# LDVBug_Hauptplatine.net
KiCad netlist of a schematic drawn in EAGLE
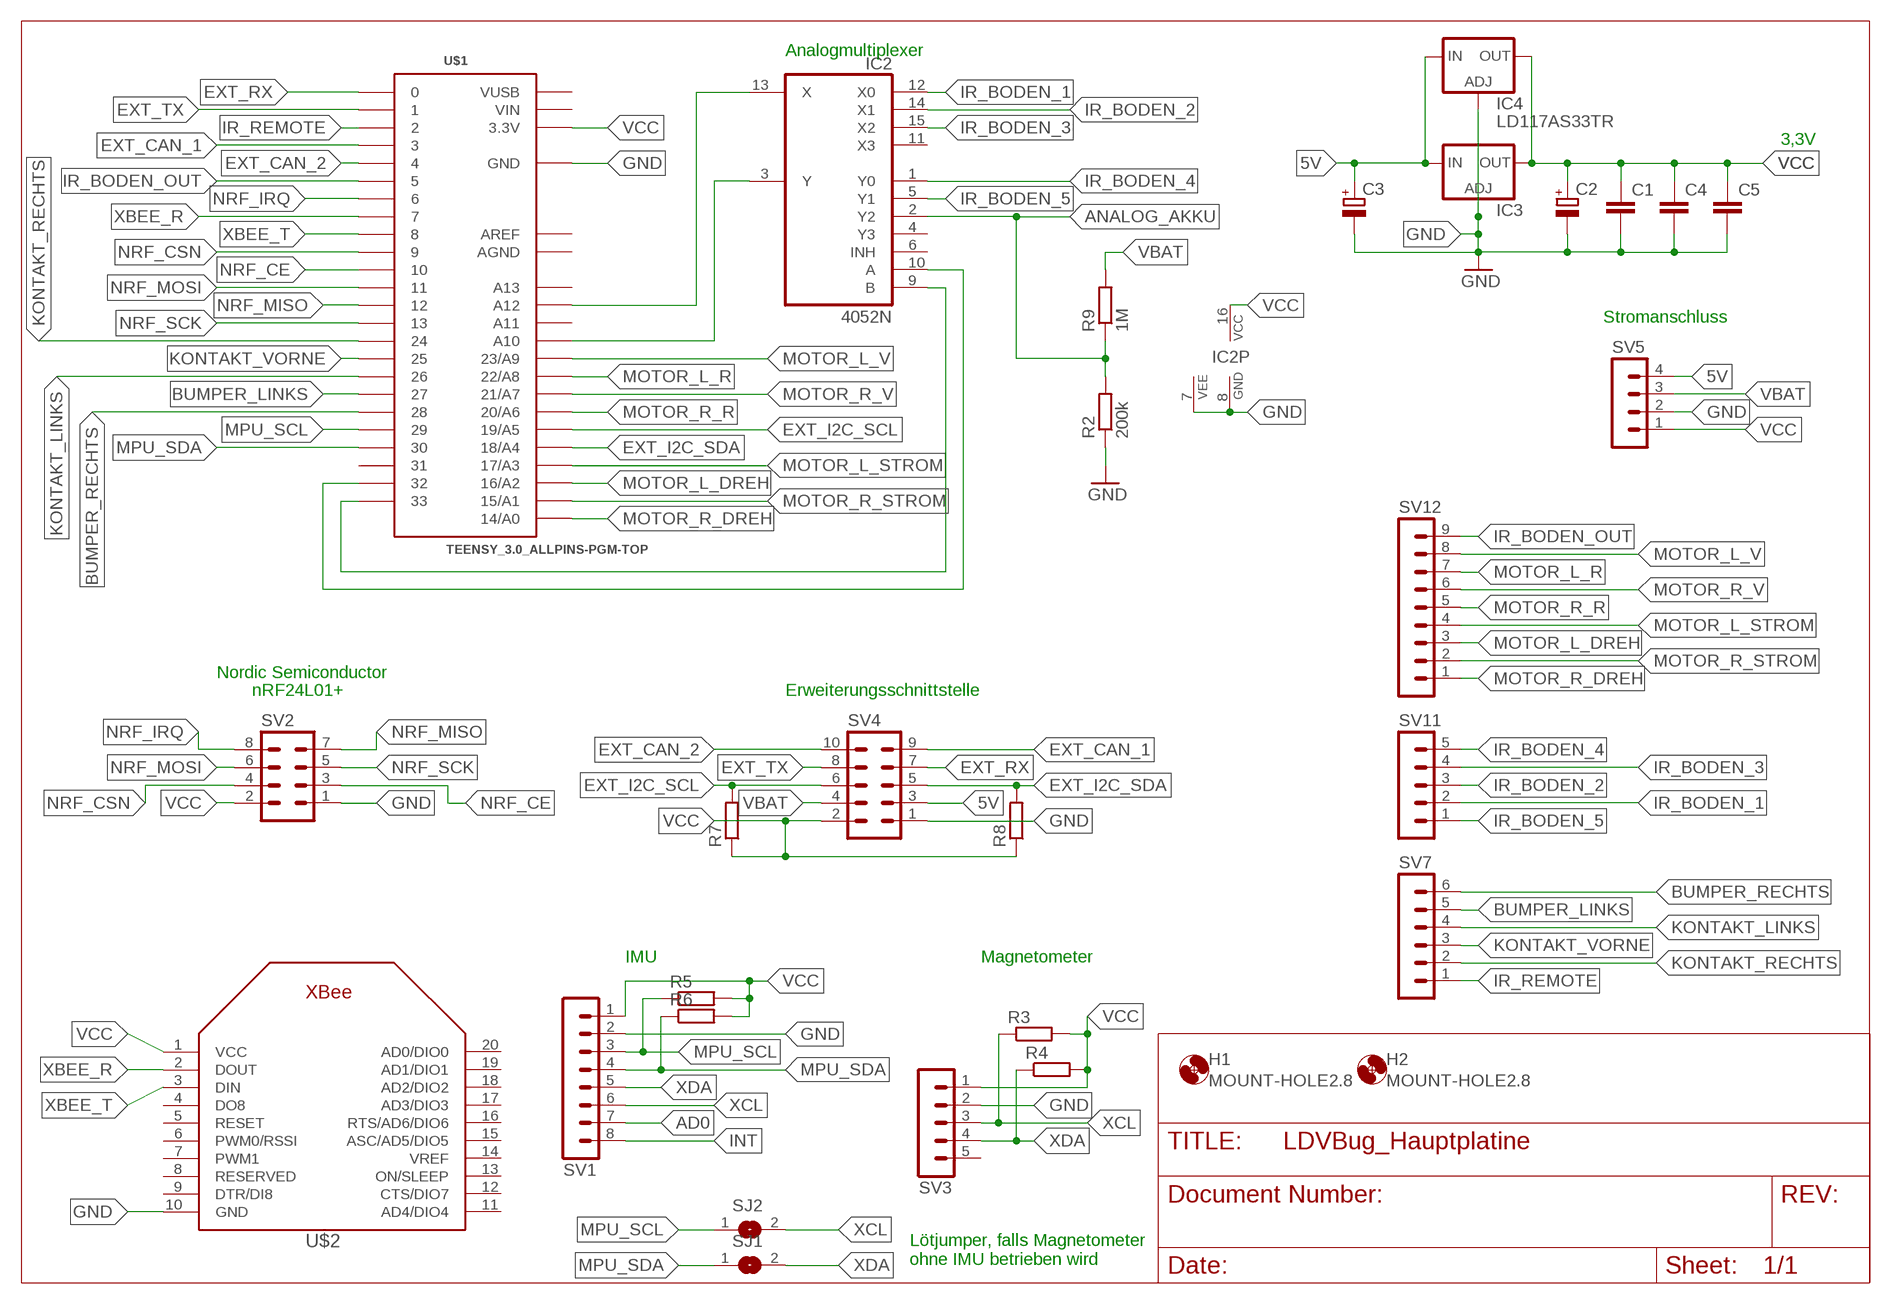
[diagram p0: schematic, sheet 1]

(export (version "E")
  (design (tool "Eeschema 10.0.6"))
  (components
    (comp (ref "C1")
      (value "C-EU025-025X050")
      (footprint "eagle-import:C025-025X050")
      (libsource (lib "eagle-import") (part "C-EU025-025X050"))
    )
    (comp (ref "C2")
      (value "CPOL-EUE2.5-7")
      (footprint "eagle-import:E2,5-7")
      (libsource (lib "eagle-import") (part "CPOL-EUE2.5-7"))
    )
    (comp (ref "C3")
      (value "CPOL-EUE2.5-7")
      (footprint "eagle-import:E2,5-7")
      (libsource (lib "eagle-import") (part "CPOL-EUE2.5-7"))
    )
    (comp (ref "C4")
      (value "C-EU025-025X050")
      (footprint "eagle-import:C025-025X050")
      (libsource (lib "eagle-import") (part "C-EU025-025X050"))
    )
    (comp (ref "C5")
      (value "C-EU025-025X050")
      (footprint "eagle-import:C025-025X050")
      (libsource (lib "eagle-import") (part "C-EU025-025X050"))
    )
    (comp (ref "H1")
      (value "MOUNT-HOLE2.8")
      (footprint "eagle-import:2,8")
      (libsource (lib "eagle-import") (part "MOUNT-HOLE2.8"))
    )
    (comp (ref "H2")
      (value "MOUNT-HOLE2.8")
      (footprint "eagle-import:2,8")
      (libsource (lib "eagle-import") (part "MOUNT-HOLE2.8"))
    )
    (comp (ref "IC2")
      (value "4052N")
      (footprint "eagle-import:DIL16")
      (libsource (lib "eagle-import") (part "4052N"))
    )
    (comp (ref "IC3")
      (value "LM317TS")
      (footprint "eagle-import:317TS")
      (libsource (lib "eagle-import") (part "LM317TS"))
    )
    (comp (ref "IC4")
      (value "LD117AS33TR")
      (footprint "eagle-import:SOT223")
      (libsource (lib "eagle-import") (part "LD117A?S33TR"))
    )
    (comp (ref "R2")
      (value "200k")
      (footprint "eagle-import:0207_10")
      (libsource (lib "eagle-import") (part "R-EU_0207/10"))
    )
    (comp (ref "R3")
      (value "R-EU_R0805")
      (footprint "eagle-import:R0805")
      (libsource (lib "eagle-import") (part "R-EU_R0805"))
    )
    (comp (ref "R4")
      (value "R-EU_R0805")
      (footprint "eagle-import:R0805")
      (libsource (lib "eagle-import") (part "R-EU_R0805"))
    )
    (comp (ref "R5")
      (value "R-EU_R0805")
      (footprint "eagle-import:R0805")
      (libsource (lib "eagle-import") (part "R-EU_R0805"))
    )
    (comp (ref "R6")
      (value "R-EU_R0805")
      (footprint "eagle-import:R0805")
      (libsource (lib "eagle-import") (part "R-EU_R0805"))
    )
    (comp (ref "R7")
      (value "R-EU_R0805")
      (footprint "eagle-import:R0805")
      (libsource (lib "eagle-import") (part "R-EU_R0805"))
    )
    (comp (ref "R8")
      (value "R-EU_R0805")
      (footprint "eagle-import:R0805")
      (libsource (lib "eagle-import") (part "R-EU_R0805"))
    )
    (comp (ref "R9")
      (value "1M")
      (footprint "eagle-import:0207_15")
      (libsource (lib "eagle-import") (part "R-EU_0207/18"))
    )
    (comp (ref "SJ1") (value "SJ") (footprint "eagle-import:SJ") (libsource (lib "eagle-import") (part "SJ")))
    (comp (ref "SJ2") (value "SJ") (footprint "eagle-import:SJ") (libsource (lib "eagle-import") (part "SJ")))
    (comp (ref "SV1")
      (value "MA08-1")
      (footprint "eagle-import:MA08-1")
      (libsource (lib "eagle-import") (part "MA08-1"))
    )
    (comp (ref "SV2")
      (value "MA04-2")
      (footprint "eagle-import:MA04-2")
      (libsource (lib "eagle-import") (part "MA04-2"))
    )
    (comp (ref "SV3")
      (value "MA05-1")
      (footprint "eagle-import:MA05-1")
      (libsource (lib "eagle-import") (part "MA05-1"))
    )
    (comp (ref "SV4")
      (value "MA05-2")
      (footprint "eagle-import:MA05-2")
      (libsource (lib "eagle-import") (part "MA05-2"))
    )
    (comp (ref "SV5")
      (value "MA04-1")
      (footprint "eagle-import:MA04-1")
      (libsource (lib "eagle-import") (part "MA04-1"))
    )
    (comp (ref "SV7")
      (value "MA06-1")
      (footprint "eagle-import:MA06-1")
      (libsource (lib "eagle-import") (part "MA06-1"))
    )
    (comp (ref "SV11")
      (value "MA05-1")
      (footprint "eagle-import:MA05-1")
      (libsource (lib "eagle-import") (part "MA05-1"))
    )
    (comp (ref "SV12")
      (value "MA09-1")
      (footprint "eagle-import:MA09-1")
      (libsource (lib "eagle-import") (part "MA09-1"))
    )
    (comp (ref "U$1")
      (value "TEENSY_3.0_ALLPINS-PGM-TOP")
      (footprint "eagle-import:TEENSY_3.0_ALLPINS-PGM")
      (libsource (lib "eagle-import") (part "TEENSY_3.0_ALLPINS-PGM-TOP"))
    )
    (comp (ref "U$2")
      (value "XBEE")
      (footprint "eagle-import:XBEE")
      (libsource (lib "eagle-import") (part "XBEE"))
    )
  )
  (nets
    (net (code "1") (name "/AGND") (class "Default")
      (node (ref "U$1") (pin "AGND") (pinfunction "AGND_AGND") (pintype "power_in"))
    )
    (net (code "2") (name "/AREF") (class "Default")
      (node (ref "U$1") (pin "AREF") (pinfunction "AREF_AREF") (pintype "power_in"))
    )
    (net (code "3") (name "/VIN") (class "Default")
      (node (ref "U$1") (pin "VIN") (pinfunction "VIN_VIN") (pintype "power_in"))
    )
    (net (code "4") (name "/VUSB") (class "Default")
      (node (ref "U$1") (pin "VUSB") (pinfunction "VUSB_VUSB") (pintype "power_in"))
    )
    (net (code "5") (name "5V") (class "Default")
      (node (ref "C3") (pin "+") (pinfunction "+_+") (pintype "passive"))
      (node (ref "IC3") (pin "3") (pinfunction "IN_3") (pintype "input"))
      (node (ref "IC4") (pin "3") (pinfunction "IN_3") (pintype "input"))
      (node (ref "SV4") (pin "3") (pinfunction "3_3") (pintype "passive"))
      (node (ref "SV5") (pin "4") (pinfunction "4_4") (pintype "passive"))
    )
    (net (code "6") (name "AD0") (class "Default")
      (node (ref "SV1") (pin "7") (pinfunction "7_7") (pintype "passive"))
    )
    (net (code "7") (name "ANALOG_AKKU") (class "Default")
      (node (ref "IC2") (pin "2") (pinfunction "Y2_2") (pintype "bidirectional"))
      (node (ref "R2") (pin "2") (pinfunction "2_2") (pintype "passive"))
      (node (ref "R9") (pin "1") (pinfunction "1_1") (pintype "passive"))
    )
    (net (code "8") (name "BUMPER_LINKS") (class "Default")
      (node (ref "SV7") (pin "5") (pinfunction "5_5") (pintype "passive"))
      (node (ref "U$1") (pin "27") (pinfunction "27_27") (pintype "bidirectional"))
    )
    (net (code "9") (name "BUMPER_RECHTS") (class "Default")
      (node (ref "SV7") (pin "6") (pinfunction "6_6") (pintype "passive"))
      (node (ref "U$1") (pin "28") (pinfunction "28_28") (pintype "bidirectional"))
    )
    (net (code "10") (name "EXT_CAN_1") (class "Default")
      (node (ref "SV4") (pin "9") (pinfunction "9_9") (pintype "passive"))
      (node (ref "U$1") (pin "3") (pinfunction "3_3") (pintype "bidirectional"))
    )
    (net (code "11") (name "EXT_CAN_2") (class "Default")
      (node (ref "SV4") (pin "10") (pinfunction "10_10") (pintype "passive"))
      (node (ref "U$1") (pin "4") (pinfunction "4_4") (pintype "bidirectional"))
    )
    (net (code "12") (name "EXT_I2C_SCL") (class "Default")
      (node (ref "R7") (pin "2") (pinfunction "2_2") (pintype "passive"))
      (node (ref "SV4") (pin "6") (pinfunction "6_6") (pintype "passive"))
      (node (ref "U$1") (pin "19/A5") (pinfunction "19/A5_19/A5") (pintype "bidirectional"))
    )
    (net (code "13") (name "EXT_I2C_SDA") (class "Default")
      (node (ref "R8") (pin "2") (pinfunction "2_2") (pintype "passive"))
      (node (ref "SV4") (pin "5") (pinfunction "5_5") (pintype "passive"))
      (node (ref "U$1") (pin "18/A4") (pinfunction "18/A4_18/A4") (pintype "bidirectional"))
    )
    (net (code "14") (name "EXT_RX") (class "Default")
      (node (ref "SV4") (pin "7") (pinfunction "7_7") (pintype "passive"))
      (node (ref "U$1") (pin "0") (pinfunction "0_0") (pintype "bidirectional"))
    )
    (net (code "15") (name "EXT_TX") (class "Default")
      (node (ref "SV4") (pin "8") (pinfunction "8_8") (pintype "passive"))
      (node (ref "U$1") (pin "1") (pinfunction "1_1") (pintype "bidirectional"))
    )
    (net (code "16") (name "GND") (class "Default")
      (node (ref "C1") (pin "2") (pinfunction "2_2") (pintype "passive"))
      (node (ref "C2") (pin "-") (pinfunction "-_-") (pintype "passive"))
      (node (ref "C3") (pin "-") (pinfunction "-_-") (pintype "passive"))
      (node (ref "C4") (pin "2") (pinfunction "2_2") (pintype "passive"))
      (node (ref "C5") (pin "2") (pinfunction "2_2") (pintype "passive"))
      (node (ref "IC2") (pin "7") (pinfunction "VEE_7") (pintype "power_in"))
      (node (ref "IC2") (pin "8") (pinfunction "GND_8") (pintype "power_in"))
      (node (ref "IC3") (pin "1") (pinfunction "ADJ_1") (pintype "input"))
      (node (ref "IC4") (pin "1") (pinfunction "ADJ_1") (pintype "input"))
      (node (ref "R2") (pin "1") (pinfunction "1_1") (pintype "passive"))
      (node (ref "SV1") (pin "2") (pinfunction "2_2") (pintype "passive"))
      (node (ref "SV2") (pin "1") (pinfunction "1_1") (pintype "passive"))
      (node (ref "SV3") (pin "2") (pinfunction "2_2") (pintype "passive"))
      (node (ref "SV4") (pin "1") (pinfunction "1_1") (pintype "passive"))
      (node (ref "SV5") (pin "2") (pinfunction "2_2") (pintype "passive"))
      (node (ref "U$1") (pin "GND") (pinfunction "GND_GND") (pintype "power_in"))
      (node (ref "U$1") (pin "GND2") (pinfunction "GND_GND2") (pintype "power_in"))
      (node (ref "U$2") (pin "10") (pinfunction "GND_10") (pintype "power_in"))
    )
    (net (code "17") (name "INT") (class "Default")
      (node (ref "SV1") (pin "8") (pinfunction "8_8") (pintype "passive"))
    )
    (net (code "18") (name "IR_BODEN_1") (class "Default")
      (node (ref "IC2") (pin "12") (pinfunction "X0_12") (pintype "bidirectional"))
      (node (ref "SV11") (pin "2") (pinfunction "2_2") (pintype "passive"))
    )
    (net (code "19") (name "IR_BODEN_2") (class "Default")
      (node (ref "IC2") (pin "14") (pinfunction "X1_14") (pintype "bidirectional"))
      (node (ref "SV11") (pin "3") (pinfunction "3_3") (pintype "passive"))
    )
    (net (code "20") (name "IR_BODEN_3") (class "Default")
      (node (ref "IC2") (pin "15") (pinfunction "X2_15") (pintype "bidirectional"))
      (node (ref "SV11") (pin "4") (pinfunction "4_4") (pintype "passive"))
    )
    (net (code "21") (name "IR_BODEN_4") (class "Default")
      (node (ref "IC2") (pin "1") (pinfunction "Y0_1") (pintype "bidirectional"))
      (node (ref "SV11") (pin "5") (pinfunction "5_5") (pintype "passive"))
    )
    (net (code "22") (name "IR_BODEN_5") (class "Default")
      (node (ref "IC2") (pin "5") (pinfunction "Y1_5") (pintype "bidirectional"))
      (node (ref "SV11") (pin "1") (pinfunction "1_1") (pintype "passive"))
    )
    (net (code "23") (name "IR_BODEN_OUT") (class "Default")
      (node (ref "SV12") (pin "9") (pinfunction "9_9") (pintype "passive"))
      (node (ref "U$1") (pin "5") (pinfunction "5_5") (pintype "bidirectional"))
    )
    (net (code "24") (name "IR_REMOTE") (class "Default")
      (node (ref "SV7") (pin "1") (pinfunction "1_1") (pintype "passive"))
      (node (ref "U$1") (pin "2") (pinfunction "2_2") (pintype "bidirectional"))
    )
    (net (code "25") (name "KONTAKT_LINKS") (class "Default")
      (node (ref "SV7") (pin "4") (pinfunction "4_4") (pintype "passive"))
      (node (ref "U$1") (pin "26") (pinfunction "26_26") (pintype "bidirectional"))
    )
    (net (code "26") (name "KONTAKT_RECHTS") (class "Default")
      (node (ref "SV7") (pin "2") (pinfunction "2_2") (pintype "passive"))
      (node (ref "U$1") (pin "24") (pinfunction "24_24") (pintype "bidirectional"))
    )
    (net (code "27") (name "KONTAKT_VORNE") (class "Default")
      (node (ref "SV7") (pin "3") (pinfunction "3_3") (pintype "passive"))
      (node (ref "U$1") (pin "25") (pinfunction "25_25") (pintype "bidirectional"))
    )
    (net (code "28") (name "MOTOR_L_DREH") (class "Default")
      (node (ref "SV12") (pin "3") (pinfunction "3_3") (pintype "passive"))
      (node (ref "U$1") (pin "16/A2") (pinfunction "16/A2_16/A2") (pintype "bidirectional"))
    )
    (net (code "29") (name "MOTOR_L_R") (class "Default")
      (node (ref "SV12") (pin "7") (pinfunction "7_7") (pintype "passive"))
      (node (ref "U$1") (pin "22/A8") (pinfunction "22/A8_22/A8") (pintype "bidirectional"))
    )
    (net (code "30") (name "MOTOR_L_STROM") (class "Default")
      (node (ref "SV12") (pin "4") (pinfunction "4_4") (pintype "passive"))
      (node (ref "U$1") (pin "17/A3") (pinfunction "17/A3_17/A3") (pintype "bidirectional"))
    )
    (net (code "31") (name "MOTOR_L_V") (class "Default")
      (node (ref "SV12") (pin "8") (pinfunction "8_8") (pintype "passive"))
      (node (ref "U$1") (pin "23/A9") (pinfunction "23/A9_23/A9") (pintype "bidirectional"))
    )
    (net (code "32") (name "MOTOR_R_DREH") (class "Default")
      (node (ref "SV12") (pin "1") (pinfunction "1_1") (pintype "passive"))
      (node (ref "U$1") (pin "14/A0") (pinfunction "14/A0_14/A0") (pintype "bidirectional"))
    )
    (net (code "33") (name "MOTOR_R_R") (class "Default")
      (node (ref "SV12") (pin "5") (pinfunction "5_5") (pintype "passive"))
      (node (ref "U$1") (pin "20/A6") (pinfunction "20/A6_20/A6") (pintype "bidirectional"))
    )
    (net (code "34") (name "MOTOR_R_STROM") (class "Default")
      (node (ref "SV12") (pin "2") (pinfunction "2_2") (pintype "passive"))
      (node (ref "U$1") (pin "15/A1") (pinfunction "15/A1_15/A1") (pintype "bidirectional"))
    )
    (net (code "35") (name "MOTOR_R_V") (class "Default")
      (node (ref "SV12") (pin "6") (pinfunction "6_6") (pintype "passive"))
      (node (ref "U$1") (pin "21/A7") (pinfunction "21/A7_21/A7") (pintype "bidirectional"))
    )
    (net (code "36") (name "MPU_SCL") (class "Default")
      (node (ref "R5") (pin "1") (pinfunction "1_1") (pintype "passive"))
      (node (ref "SJ2") (pin "1") (pinfunction "1_1") (pintype "passive"))
      (node (ref "SV1") (pin "3") (pinfunction "3_3") (pintype "passive"))
      (node (ref "U$1") (pin "29") (pinfunction "29_29") (pintype "bidirectional"))
    )
    (net (code "37") (name "MPU_SDA") (class "Default")
      (node (ref "R6") (pin "1") (pinfunction "1_1") (pintype "passive"))
      (node (ref "SJ1") (pin "1") (pinfunction "1_1") (pintype "passive"))
      (node (ref "SV1") (pin "4") (pinfunction "4_4") (pintype "passive"))
      (node (ref "U$1") (pin "30") (pinfunction "30_30") (pintype "bidirectional"))
    )
    (net (code "38") (name "NRF_CE") (class "Default")
      (node (ref "SV2") (pin "3") (pinfunction "3_3") (pintype "passive"))
      (node (ref "U$1") (pin "10") (pinfunction "10_10") (pintype "bidirectional"))
    )
    (net (code "39") (name "NRF_CSN") (class "Default")
      (node (ref "SV2") (pin "4") (pinfunction "4_4") (pintype "passive"))
      (node (ref "U$1") (pin "9") (pinfunction "9_9") (pintype "bidirectional"))
    )
    (net (code "40") (name "NRF_IRQ") (class "Default")
      (node (ref "SV2") (pin "8") (pinfunction "8_8") (pintype "passive"))
      (node (ref "U$1") (pin "6") (pinfunction "6_6") (pintype "bidirectional"))
    )
    (net (code "41") (name "NRF_MISO") (class "Default")
      (node (ref "SV2") (pin "7") (pinfunction "7_7") (pintype "passive"))
      (node (ref "U$1") (pin "12") (pinfunction "12_12") (pintype "bidirectional"))
    )
    (net (code "42") (name "NRF_MOSI") (class "Default")
      (node (ref "SV2") (pin "6") (pinfunction "6_6") (pintype "passive"))
      (node (ref "U$1") (pin "11") (pinfunction "11_11") (pintype "bidirectional"))
    )
    (net (code "43") (name "NRF_SCK") (class "Default")
      (node (ref "SV2") (pin "5") (pinfunction "5_5") (pintype "passive"))
      (node (ref "U$1") (pin "13") (pinfunction "13_13") (pintype "bidirectional"))
    )
    (net (code "44") (name "Net-(IC2A-A)") (class "Default")
      (node (ref "IC2") (pin "10") (pinfunction "A_10") (pintype "input"))
      (node (ref "U$1") (pin "32") (pinfunction "32_32") (pintype "bidirectional"))
    )
    (net (code "45") (name "Net-(IC2A-B)") (class "Default")
      (node (ref "IC2") (pin "9") (pinfunction "B_9") (pintype "input"))
      (node (ref "U$1") (pin "33") (pinfunction "33_33") (pintype "bidirectional"))
    )
    (net (code "46") (name "Net-(IC2A-X)") (class "Default")
      (node (ref "IC2") (pin "13") (pinfunction "X_13") (pintype "bidirectional"))
      (node (ref "U$1") (pin "A12") (pinfunction "A12_A12") (pintype "bidirectional"))
    )
    (net (code "47") (name "Net-(IC2A-Y)") (class "Default")
      (node (ref "IC2") (pin "3") (pinfunction "Y_3") (pintype "bidirectional"))
      (node (ref "U$1") (pin "A10") (pinfunction "A10_A10") (pintype "bidirectional"))
    )
    (net (code "48") (name "VBAT") (class "Default")
      (node (ref "R9") (pin "2") (pinfunction "2_2") (pintype "passive"))
      (node (ref "SV4") (pin "4") (pinfunction "4_4") (pintype "passive"))
      (node (ref "SV5") (pin "3") (pinfunction "3_3") (pintype "passive"))
    )
    (net (code "49") (name "VCC") (class "Default")
      (node (ref "C1") (pin "1") (pinfunction "1_1") (pintype "passive"))
      (node (ref "C2") (pin "+") (pinfunction "+_+") (pintype "passive"))
      (node (ref "C4") (pin "1") (pinfunction "1_1") (pintype "passive"))
      (node (ref "C5") (pin "1") (pinfunction "1_1") (pintype "passive"))
      (node (ref "IC2") (pin "16") (pinfunction "VCC_16") (pintype "power_in"))
      (node (ref "IC3") (pin "2") (pinfunction "OUT_2") (pintype "passive"))
      (node (ref "IC4") (pin "4") (pinfunction "OUT_4") (pintype "passive"))
      (node (ref "R3") (pin "2") (pinfunction "2_2") (pintype "passive"))
      (node (ref "R4") (pin "2") (pinfunction "2_2") (pintype "passive"))
      (node (ref "R5") (pin "2") (pinfunction "2_2") (pintype "passive"))
      (node (ref "R6") (pin "2") (pinfunction "2_2") (pintype "passive"))
      (node (ref "R7") (pin "1") (pinfunction "1_1") (pintype "passive"))
      (node (ref "R8") (pin "1") (pinfunction "1_1") (pintype "passive"))
      (node (ref "SV1") (pin "1") (pinfunction "1_1") (pintype "passive"))
      (node (ref "SV2") (pin "2") (pinfunction "2_2") (pintype "passive"))
      (node (ref "SV3") (pin "1") (pinfunction "1_1") (pintype "passive"))
      (node (ref "SV4") (pin "2") (pinfunction "2_2") (pintype "passive"))
      (node (ref "SV5") (pin "1") (pinfunction "1_1") (pintype "passive"))
      (node (ref "U$1") (pin "3.3V") (pinfunction "3.3V_3.3V") (pintype "power_in"))
      (node (ref "U$1") (pin "3.3V2") (pinfunction "3.3V_3.3V2") (pintype "power_in"))
      (node (ref "U$2") (pin "1") (pinfunction "VCC_1") (pintype "power_in"))
    )
    (net (code "50") (name "XBEE_R") (class "Default")
      (node (ref "U$1") (pin "7") (pinfunction "7_7") (pintype "bidirectional"))
      (node (ref "U$2") (pin "2") (pinfunction "DOUT_2") (pintype "output"))
    )
    (net (code "51") (name "XBEE_T") (class "Default")
      (node (ref "U$1") (pin "8") (pinfunction "8_8") (pintype "bidirectional"))
      (node (ref "U$2") (pin "3") (pinfunction "DIN_3") (pintype "input"))
    )
    (net (code "52") (name "XCL") (class "Default")
      (node (ref "R3") (pin "1") (pinfunction "1_1") (pintype "passive"))
      (node (ref "SJ2") (pin "2") (pinfunction "2_2") (pintype "passive"))
      (node (ref "SV1") (pin "6") (pinfunction "6_6") (pintype "passive"))
      (node (ref "SV3") (pin "3") (pinfunction "3_3") (pintype "passive"))
    )
    (net (code "53") (name "XDA") (class "Default")
      (node (ref "R4") (pin "1") (pinfunction "1_1") (pintype "passive"))
      (node (ref "SJ1") (pin "2") (pinfunction "2_2") (pintype "passive"))
      (node (ref "SV1") (pin "5") (pinfunction "5_5") (pintype "passive"))
      (node (ref "SV3") (pin "4") (pinfunction "4_4") (pintype "passive"))
    )
    (net (code "54") (name "unconnected-(IC2A-INH-Pad6)") (class "Default")
      (node (ref "IC2") (pin "6") (pinfunction "INH_6") (pintype "input"))
    )
    (net (code "55") (name "unconnected-(IC2A-X3-Pad11)") (class "Default")
      (node (ref "IC2") (pin "11") (pinfunction "X3_11") (pintype "bidirectional"))
    )
    (net (code "56") (name "unconnected-(IC2A-Y3-Pad4)") (class "Default")
      (node (ref "IC2") (pin "4") (pinfunction "Y3_4") (pintype "bidirectional"))
    )
    (net (code "57") (name "unconnected-(SV3-Pad5)") (class "Default")
      (node (ref "SV3") (pin "5") (pinfunction "5_5") (pintype "passive"))
    )
    (net (code "58") (name "unconnected-(U$1-Pad31)") (class "Default")
      (node (ref "U$1") (pin "31") (pinfunction "31_31") (pintype "bidirectional"))
    )
    (net (code "59") (name "unconnected-(U$1-PadA11)") (class "Default")
      (node (ref "U$1") (pin "A11") (pinfunction "A11_A11") (pintype "bidirectional"))
    )
    (net (code "60") (name "unconnected-(U$1-PadA13)") (class "Default")
      (node (ref "U$1") (pin "A13") (pinfunction "A13_A13") (pintype "bidirectional"))
    )
    (net (code "61") (name "unconnected-(U$2-AD0{slash}DIO0-Pad20)") (class "Default")
      (node (ref "U$2") (pin "20") (pinfunction "AD0/DIO0_20") (pintype "bidirectional"))
    )
    (net (code "62") (name "unconnected-(U$2-AD1{slash}DIO1-Pad19)") (class "Default")
      (node (ref "U$2") (pin "19") (pinfunction "AD1/DIO1_19") (pintype "bidirectional"))
    )
    (net (code "63") (name "unconnected-(U$2-AD2{slash}DIO2-Pad18)") (class "Default")
      (node (ref "U$2") (pin "18") (pinfunction "AD2/DIO2_18") (pintype "bidirectional"))
    )
    (net (code "64") (name "unconnected-(U$2-AD3{slash}DIO3-Pad17)") (class "Default")
      (node (ref "U$2") (pin "17") (pinfunction "AD3/DIO3_17") (pintype "bidirectional"))
    )
    (net (code "65") (name "unconnected-(U$2-AD4{slash}DIO4-Pad11)") (class "Default")
      (node (ref "U$2") (pin "11") (pinfunction "AD4/DIO4_11") (pintype "bidirectional"))
    )
    (net (code "66") (name "unconnected-(U$2-ASC{slash}AD5{slash}DIO5-Pad15)") (class "Default")
      (node (ref "U$2") (pin "15") (pinfunction "ASC/AD5/DIO5_15") (pintype "bidirectional"))
    )
    (net (code "67") (name "unconnected-(U$2-CTS{slash}DIO7-Pad12)") (class "Default")
      (node (ref "U$2") (pin "12") (pinfunction "CTS/DIO7_12") (pintype "bidirectional"))
    )
    (net (code "68") (name "unconnected-(U$2-DO8-Pad4)") (class "Default")
      (node (ref "U$2") (pin "4") (pinfunction "DO8_4") (pintype "output"))
    )
    (net (code "69") (name "unconnected-(U$2-DTR{slash}DI8-Pad9)") (class "Default")
      (node (ref "U$2") (pin "9") (pinfunction "DTR/DI8_9") (pintype "input"))
    )
    (net (code "70") (name "unconnected-(U$2-ON{slash}SLEEP-Pad13)") (class "Default")
      (node (ref "U$2") (pin "13") (pinfunction "ON/SLEEP_13") (pintype "output"))
    )
    (net (code "71") (name "unconnected-(U$2-PWM0{slash}RSSI-Pad6)") (class "Default")
      (node (ref "U$2") (pin "6") (pinfunction "PWM0/RSSI_6") (pintype "output"))
    )
    (net (code "72") (name "unconnected-(U$2-PWM1-Pad7)") (class "Default")
      (node (ref "U$2") (pin "7") (pinfunction "PWM1_7") (pintype "output"))
    )
    (net (code "73") (name "unconnected-(U$2-RESERVED-Pad8)") (class "Default")
      (node (ref "U$2") (pin "8") (pinfunction "RESERVED_8") (pintype "no_connect"))
    )
    (net (code "74") (name "unconnected-(U$2-RESET-Pad5)") (class "Default")
      (node (ref "U$2") (pin "5") (pinfunction "RESET_5") (pintype "input"))
    )
    (net (code "75") (name "unconnected-(U$2-RTS{slash}AD6{slash}DIO6-Pad16)") (class "Default")
      (node (ref "U$2") (pin "16") (pinfunction "RTS/AD6/DIO6_16") (pintype "bidirectional"))
    )
    (net (code "76") (name "unconnected-(U$2-VREF-Pad14)") (class "Default")
      (node (ref "U$2") (pin "14") (pinfunction "VREF_14") (pintype "input"))
    )
  )
)
